# 2_4G8_1.net
KiCad netlist of a schematic drawn in EasyEDA Pro
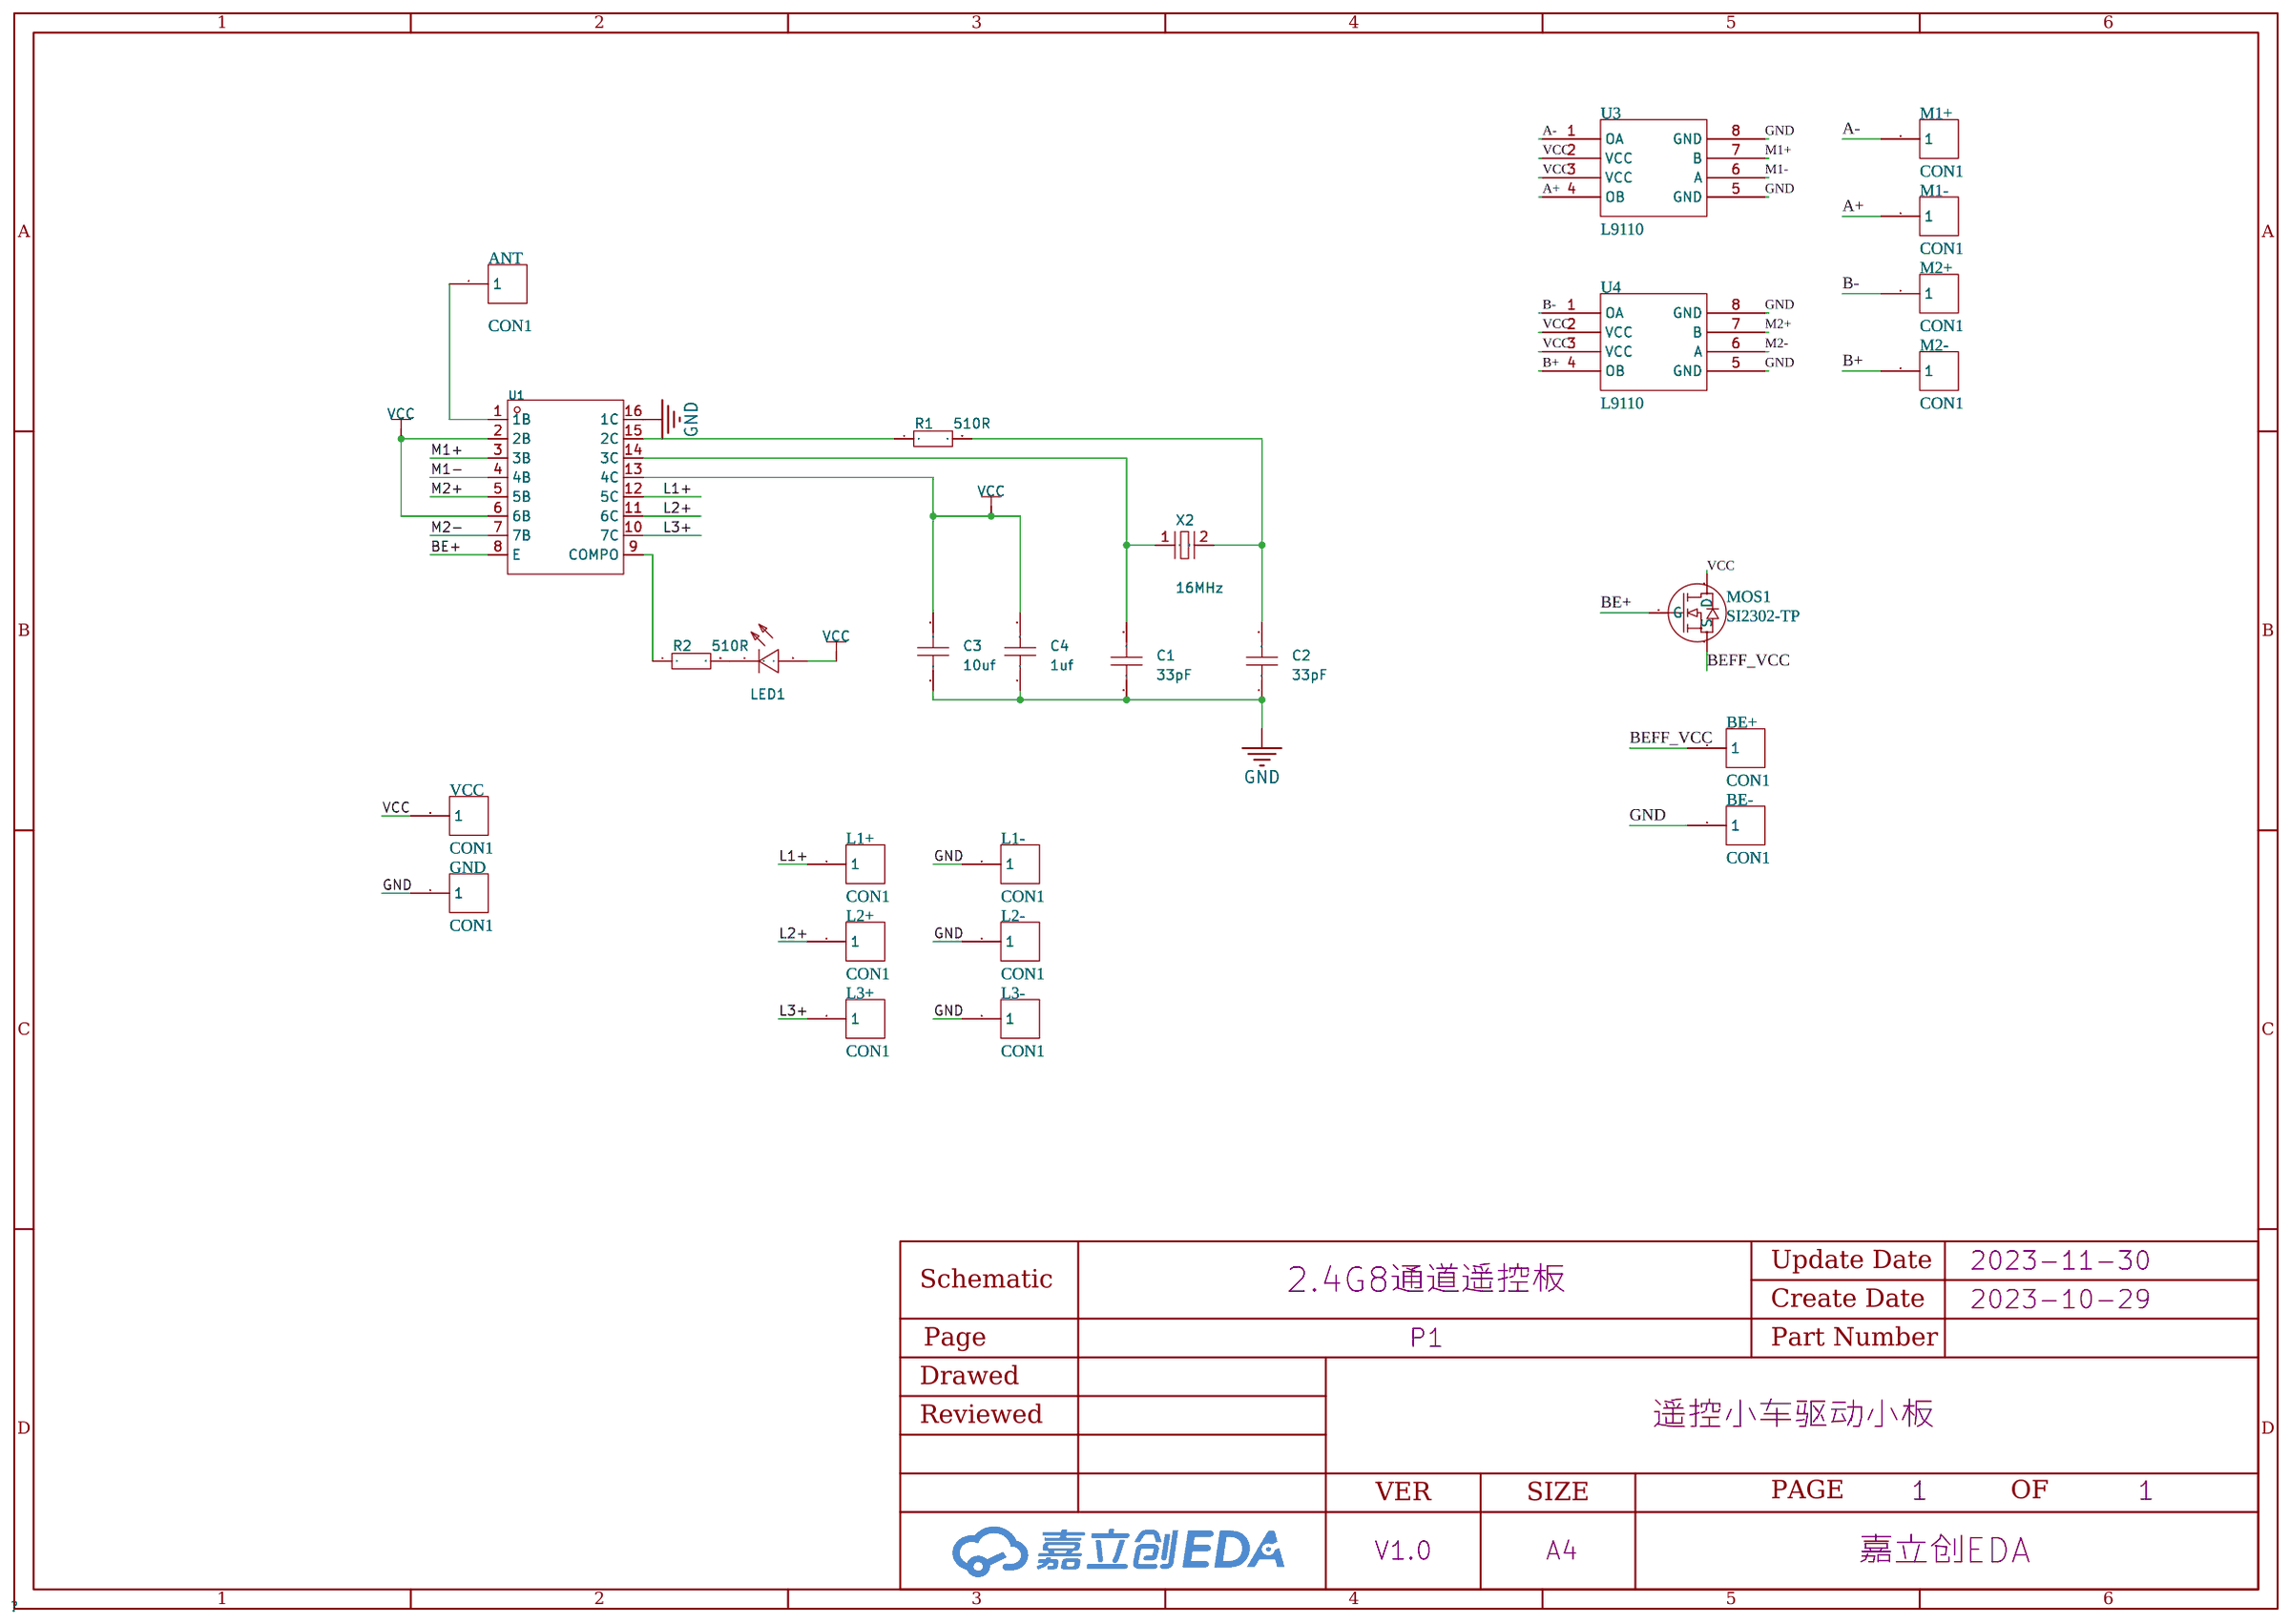
[diagram p0: schematic sheet]

(export (version "E")
  (design (tool "Eeschema 10.0.6"))
  (components
    (comp (ref "ANT")
      (value "CON1")
      (footprint "easyedapro:CON1_2")
      (libsource (lib "easyedapro") (part "CON1"))
    )
    (comp (ref "BE+")
      (value "CON1")
      (footprint "easyedapro:CON1_2")
      (libsource (lib "easyedapro") (part "CON1"))
    )
    (comp (ref "BE-")
      (value "CON1")
      (footprint "easyedapro:CON1_2")
      (libsource (lib "easyedapro") (part "CON1"))
    )
    (comp (ref "C1")
      (value "33pF")
      (footprint "easyedapro:C0603")
      (libsource (lib "easyedapro") (part "CapAcitance"))
    )
    (comp (ref "C2")
      (value "33pF")
      (footprint "easyedapro:C0603")
      (libsource (lib "easyedapro") (part "CapAcitance"))
    )
    (comp (ref "C3")
      (value "10uf")
      (footprint "easyedapro:C0603")
      (libsource (lib "easyedapro") (part "CapAcitance"))
    )
    (comp (ref "C4")
      (value "1uf")
      (footprint "easyedapro:C0603")
      (libsource (lib "easyedapro") (part "CapAcitance"))
    )
    (comp (ref "GND")
      (value "CON1")
      (footprint "easyedapro:CON1_2")
      (libsource (lib "easyedapro") (part "CON1"))
    )
    (comp (ref "L1+")
      (value "CON1")
      (footprint "easyedapro:CON1_2")
      (libsource (lib "easyedapro") (part "CON1"))
    )
    (comp (ref "L1-")
      (value "CON1")
      (footprint "easyedapro:CON1_2")
      (libsource (lib "easyedapro") (part "CON1"))
    )
    (comp (ref "L2+")
      (value "CON1")
      (footprint "easyedapro:CON1_2")
      (libsource (lib "easyedapro") (part "CON1"))
    )
    (comp (ref "L2-")
      (value "CON1")
      (footprint "easyedapro:CON1_2")
      (libsource (lib "easyedapro") (part "CON1"))
    )
    (comp (ref "L3+")
      (value "CON1")
      (footprint "easyedapro:CON1_2")
      (libsource (lib "easyedapro") (part "CON1"))
    )
    (comp (ref "L3-")
      (value "CON1")
      (footprint "easyedapro:CON1_2")
      (libsource (lib "easyedapro") (part "CON1"))
    )
    (comp (ref "LED1")
      (value "NCD0603R1")
      (footprint "easyedapro:LED0603-RD_RED")
      (description "发光颜色:红色;功率:65mW;透镜颜色:无色透明;主波长:615nm~630nm;发光强度:80mcd~220mcd;发光角度:130°;工作温度:-30°C~+85°C;")
      (fields (field (name "Manufacturer") "国星光电"))
      (libsource (lib "easyedapro") (part "FC-DA1608HRK-620D"))
    )
    (comp (ref "M1+")
      (value "CON1")
      (footprint "easyedapro:CON1_2")
      (libsource (lib "easyedapro") (part "CON1"))
    )
    (comp (ref "M1-")
      (value "CON1")
      (footprint "easyedapro:CON1_2")
      (libsource (lib "easyedapro") (part "CON1"))
    )
    (comp (ref "M2+")
      (value "CON1")
      (footprint "easyedapro:CON1_2")
      (libsource (lib "easyedapro") (part "CON1"))
    )
    (comp (ref "M2-")
      (value "CON1")
      (footprint "easyedapro:CON1_2")
      (libsource (lib "easyedapro") (part "CON1"))
    )
    (comp (ref "MOS1")
      (value "SI2302-TP")
      (footprint "easyedapro:SOT-23_MCC")
      (description "No Description Available")
      (fields (field (name "Copyright") "Copyright (C) 2022 Ultra Librarian. All rights reserved."))
      (libsource (lib "easyedapro") (part "SI2302-TP"))
    )
    (comp (ref "R1") (value "510R") (footprint "easyedapro:R0603") (libsource (lib "easyedapro") (part "电阻")))
    (comp (ref "R2") (value "510R") (footprint "easyedapro:R0603") (libsource (lib "easyedapro") (part "电阻")))
    (comp (ref "U1")
      (value "ULN2003A")
      (footprint "easyedapro:SOP-16_L10.0-W3.9-P1.27-LS6.0-BL")
      (description "开态输入电压(VI(on)@Vce,Ic):3V@2V,300mA;集射极饱和压降(VCE(sat)@Ii,Ic):900mV;开态输入电流(Ii@Vi):930uA@3.85V;")
      (fields (field (name "Manufacturer") "UMW(友台半导体)"))
      (libsource (lib "easyedapro") (part "ULN2003A_C482013"))
    )
    (comp (ref "U3")
      (value "L9110")
      (footprint "easyedapro:SOP8")
      (libsource (lib "easyedapro") (part "L9110"))
    )
    (comp (ref "U4")
      (value "L9110")
      (footprint "easyedapro:SOP8")
      (libsource (lib "easyedapro") (part "L9110"))
    )
    (comp (ref "VCC")
      (value "CON1")
      (footprint "easyedapro:CON1_2")
      (libsource (lib "easyedapro") (part "CON1"))
    )
    (comp (ref "X2")
      (value "16MHz")
      (footprint "easyedapro:CRYSTAL-TH_BD3.0-P1.10-D0.4")
      (description "频率:16MHz;频率公差:±20ppm;负载电容:20pF;")
      (fields (field (name "Manufacturer Part") "Q3816000ZWFAC") (field (name "Manufacturer") "JYJE(晶友嘉)"))
      (libsource (lib "easyedapro") (part "Q3816000ZWFAC"))
    )
  )
  (nets
    (net (code "1") (name "/A+") (class "Default")
      (node (ref "M1-") (pin "1") (pinfunction "1_1") (pintype "input"))
      (node (ref "U3") (pin "4") (pinfunction "OB_4") (pintype "input"))
    )
    (net (code "2") (name "/A-") (class "Default")
      (node (ref "M1+") (pin "1") (pinfunction "1_1") (pintype "input"))
      (node (ref "U3") (pin "1") (pinfunction "OA_1") (pintype "input"))
    )
    (net (code "3") (name "/B+") (class "Default")
      (node (ref "M2-") (pin "1") (pinfunction "1_1") (pintype "input"))
      (node (ref "U4") (pin "4") (pinfunction "OB_4") (pintype "input"))
    )
    (net (code "4") (name "/B-") (class "Default")
      (node (ref "M2+") (pin "1") (pinfunction "1_1") (pintype "input"))
      (node (ref "U4") (pin "1") (pinfunction "OA_1") (pintype "input"))
    )
    (net (code "5") (name "/BE+") (class "Default")
      (node (ref "MOS1") (pin "1") (pinfunction "G_1") (pintype "input"))
      (node (ref "U1") (pin "8") (pinfunction "E_8") (pintype "input"))
    )
    (net (code "6") (name "/BEFF_VCC") (class "Default")
      (node (ref "BE+") (pin "1") (pinfunction "1_1") (pintype "input"))
      (node (ref "MOS1") (pin "2") (pinfunction "S_2") (pintype "input"))
    )
    (net (code "7") (name "/L1+") (class "Default")
      (node (ref "L1+") (pin "1") (pinfunction "1_1") (pintype "input"))
      (node (ref "U1") (pin "12") (pinfunction "5C_12") (pintype "input"))
    )
    (net (code "8") (name "/L2+") (class "Default")
      (node (ref "L2+") (pin "1") (pinfunction "1_1") (pintype "input"))
      (node (ref "U1") (pin "11") (pinfunction "6C_11") (pintype "input"))
    )
    (net (code "9") (name "/L3+") (class "Default")
      (node (ref "L3+") (pin "1") (pinfunction "1_1") (pintype "input"))
      (node (ref "U1") (pin "10") (pinfunction "7C_10") (pintype "input"))
    )
    (net (code "10") (name "/M1+") (class "Default")
      (node (ref "U1") (pin "3") (pinfunction "3B_3") (pintype "input"))
      (node (ref "U3") (pin "7") (pinfunction "B_7") (pintype "input"))
    )
    (net (code "11") (name "/M1-") (class "Default")
      (node (ref "U1") (pin "4") (pinfunction "4B_4") (pintype "input"))
      (node (ref "U3") (pin "6") (pinfunction "A_6") (pintype "input"))
    )
    (net (code "12") (name "/M2+") (class "Default")
      (node (ref "U1") (pin "5") (pinfunction "5B_5") (pintype "input"))
      (node (ref "U4") (pin "7") (pinfunction "B_7") (pintype "input"))
    )
    (net (code "13") (name "/M2-") (class "Default")
      (node (ref "U1") (pin "7") (pinfunction "7B_7") (pintype "input"))
      (node (ref "U4") (pin "6") (pinfunction "A_6") (pintype "input"))
    )
    (net (code "14") (name "GND") (class "Default")
      (node (ref "BE-") (pin "1") (pinfunction "1_1") (pintype "input"))
      (node (ref "C1") (pin "1") (pinfunction "1_1") (pintype "input"))
      (node (ref "C2") (pin "1") (pinfunction "1_1") (pintype "input"))
      (node (ref "C3") (pin "1") (pinfunction "1_1") (pintype "input"))
      (node (ref "C4") (pin "1") (pinfunction "1_1") (pintype "input"))
      (node (ref "GND") (pin "1") (pinfunction "1_1") (pintype "input"))
      (node (ref "L1-") (pin "1") (pinfunction "1_1") (pintype "input"))
      (node (ref "L2-") (pin "1") (pinfunction "1_1") (pintype "input"))
      (node (ref "L3-") (pin "1") (pinfunction "1_1") (pintype "input"))
      (node (ref "U1") (pin "16") (pinfunction "1C_16") (pintype "input"))
      (node (ref "U3") (pin "5") (pinfunction "GND_5") (pintype "input"))
      (node (ref "U3") (pin "8") (pinfunction "GND_8") (pintype "input"))
      (node (ref "U4") (pin "5") (pinfunction "GND_5") (pintype "input"))
      (node (ref "U4") (pin "8") (pinfunction "GND_8") (pintype "input"))
    )
    (net (code "15") (name "Net-(LED1-K)") (class "Default")
      (node (ref "LED1") (pin "1") (pinfunction "K_1") (pintype "input"))
      (node (ref "R2") (pin "2") (pinfunction "2_2") (pintype "input"))
    )
    (net (code "16") (name "Net-(U1-1B)") (class "Default")
      (node (ref "ANT") (pin "1") (pinfunction "1_1") (pintype "input"))
      (node (ref "U1") (pin "1") (pinfunction "1B_1") (pintype "input"))
    )
    (net (code "17") (name "Net-(U1-2C)") (class "Default")
      (node (ref "R1") (pin "1") (pinfunction "1_1") (pintype "input"))
      (node (ref "U1") (pin "15") (pinfunction "2C_15") (pintype "input"))
    )
    (net (code "18") (name "Net-(U1-3C)") (class "Default")
      (node (ref "C1") (pin "2") (pinfunction "2_2") (pintype "input"))
      (node (ref "U1") (pin "14") (pinfunction "3C_14") (pintype "input"))
      (node (ref "X2") (pin "1") (pinfunction "1_1") (pintype "input"))
    )
    (net (code "19") (name "Net-(U1-COMPO)") (class "Default")
      (node (ref "R2") (pin "1") (pinfunction "1_1") (pintype "input"))
      (node (ref "U1") (pin "9") (pinfunction "COMPO_9") (pintype "input"))
    )
    (net (code "20") (name "Net-(X2-GND)") (class "Default")
      (node (ref "C2") (pin "2") (pinfunction "2_2") (pintype "input"))
      (node (ref "R1") (pin "2") (pinfunction "2_2") (pintype "input"))
      (node (ref "X2") (pin "2") (pinfunction "GND_2") (pintype "input"))
    )
    (net (code "21") (name "VCC") (class "Default")
      (node (ref "C3") (pin "2") (pinfunction "2_2") (pintype "input"))
      (node (ref "C4") (pin "2") (pinfunction "2_2") (pintype "input"))
      (node (ref "LED1") (pin "2") (pinfunction "A_2") (pintype "input"))
      (node (ref "MOS1") (pin "3") (pinfunction "D_3") (pintype "input"))
      (node (ref "U1") (pin "13") (pinfunction "4C_13") (pintype "input"))
      (node (ref "U1") (pin "2") (pinfunction "2B_2") (pintype "input"))
      (node (ref "U1") (pin "6") (pinfunction "6B_6") (pintype "input"))
      (node (ref "U3") (pin "2") (pinfunction "VCC_2") (pintype "input"))
      (node (ref "U3") (pin "3") (pinfunction "VCC_3") (pintype "input"))
      (node (ref "U4") (pin "2") (pinfunction "VCC_2") (pintype "input"))
      (node (ref "U4") (pin "3") (pinfunction "VCC_3") (pintype "input"))
      (node (ref "VCC") (pin "1") (pinfunction "1_1") (pintype "input"))
    )
  )
)
